# uc4h_cube_carrier_v0310r.net
KiCad netlist of a schematic drawn in EAGLE
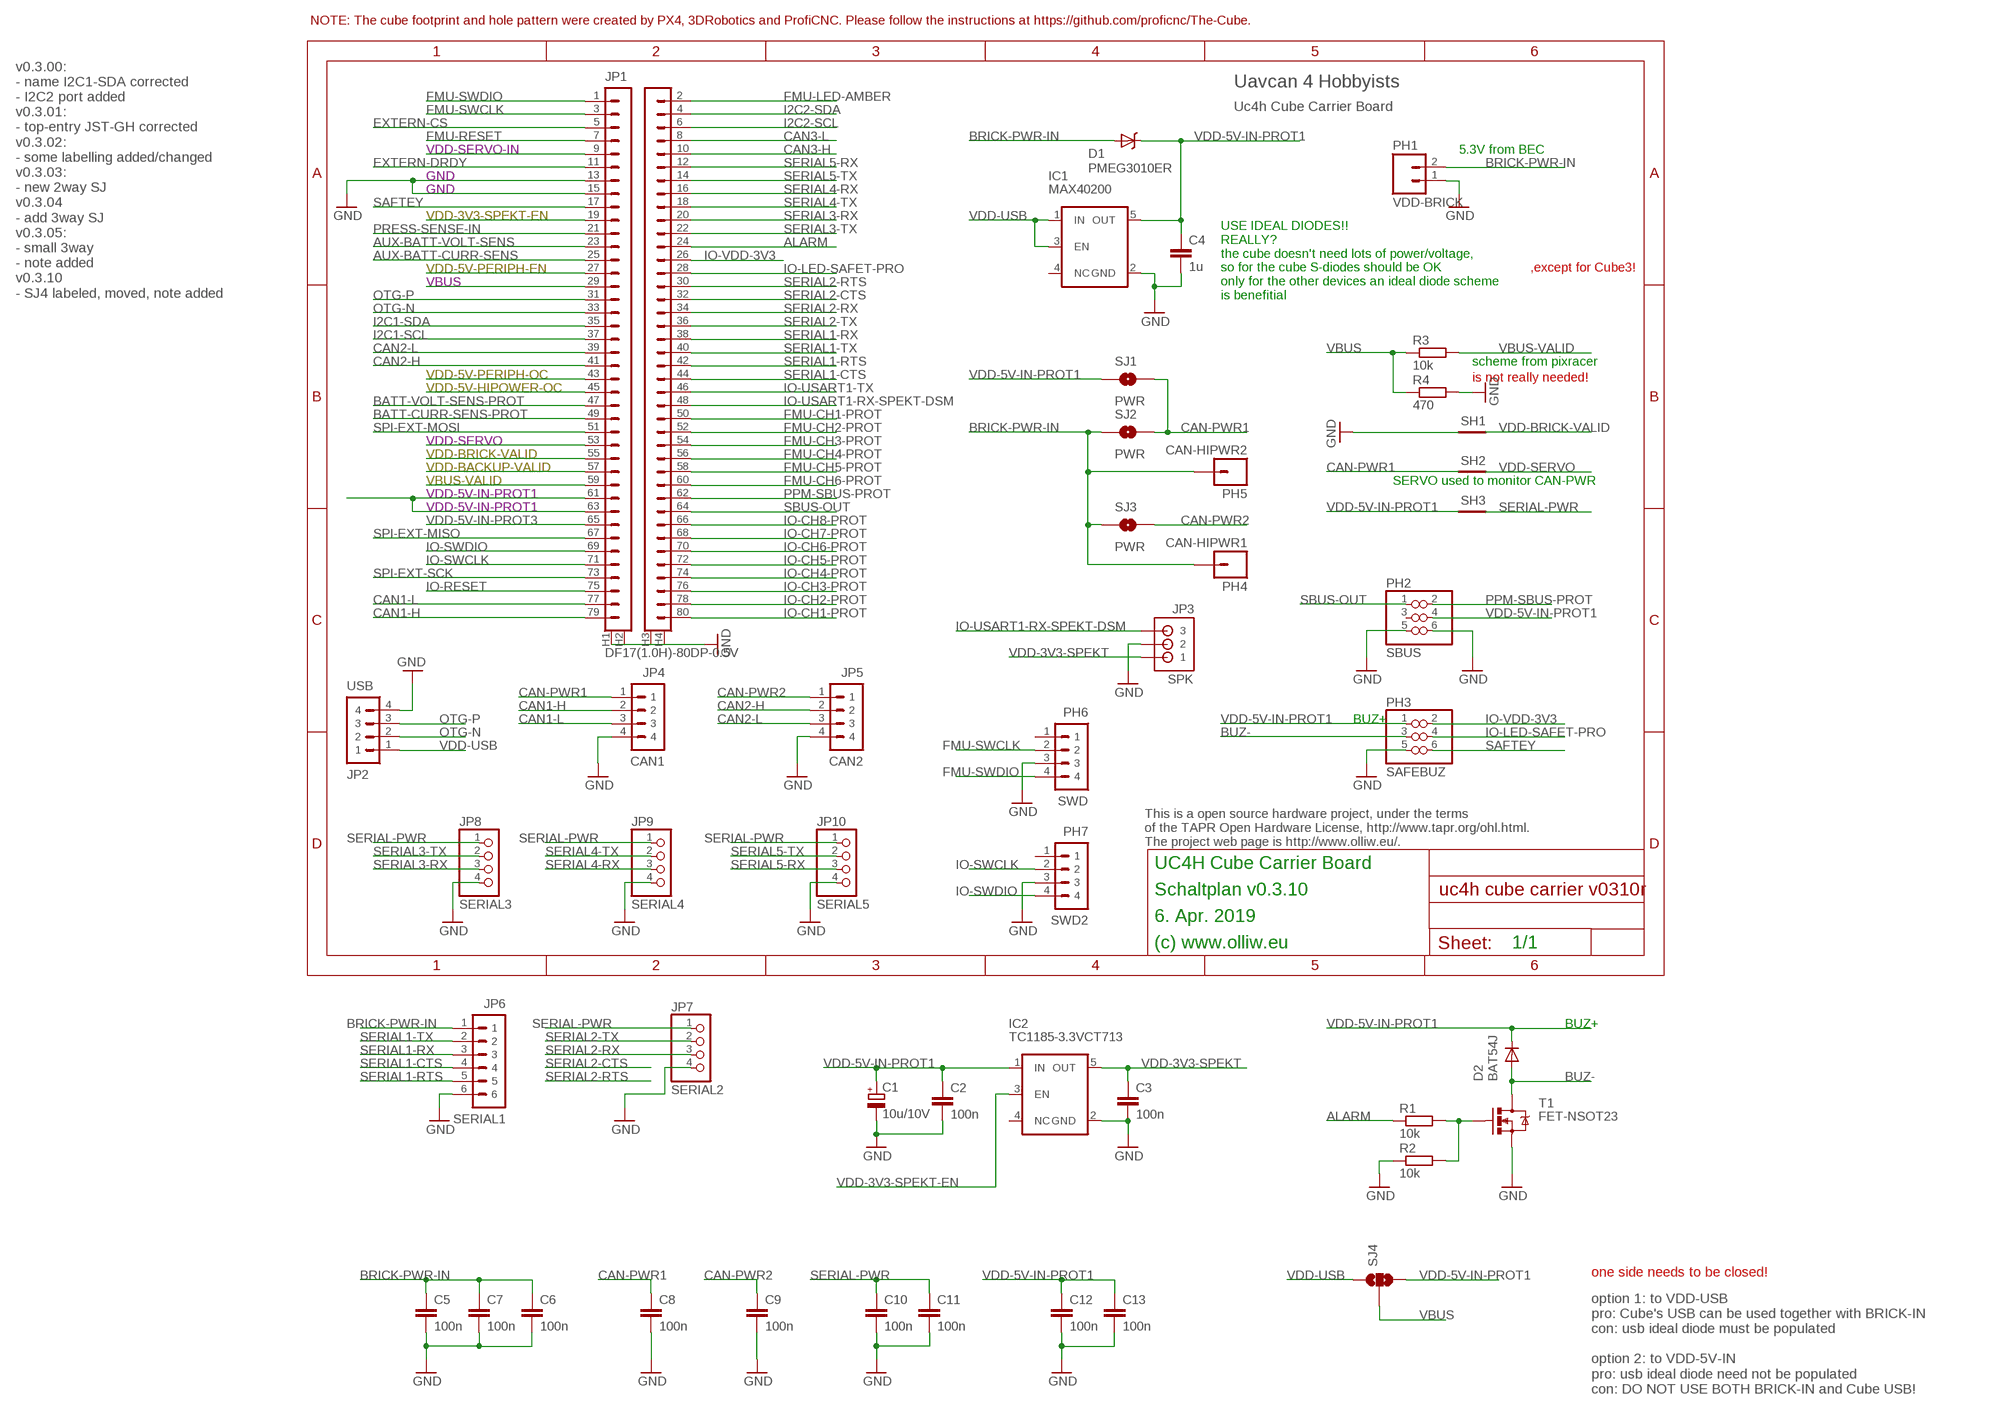
[diagram p0: schematic, sheet 1]

(export (version "E")
  (design (tool "Eeschema 10.0.6"))
  (components
    (comp (ref "C1")
      (value "10u/10V")
      (footprint "eagle-import:SMC_A")
      (libsource (lib "eagle-import") (part "CPOL-EUSMCA"))
    )
    (comp (ref "C2")
      (value "100n")
      (footprint "eagle-import:C0603")
      (libsource (lib "eagle-import") (part "C-EUC0603"))
    )
    (comp (ref "C3")
      (value "100n")
      (footprint "eagle-import:C0603")
      (libsource (lib "eagle-import") (part "C-EUC0603"))
    )
    (comp (ref "C4")
      (value "1u")
      (footprint "eagle-import:C0603")
      (libsource (lib "eagle-import") (part "C-EUC0603"))
    )
    (comp (ref "C5")
      (value "100n")
      (footprint "eagle-import:C0603")
      (libsource (lib "eagle-import") (part "C-EUC0603"))
    )
    (comp (ref "C6")
      (value "100n")
      (footprint "eagle-import:C0603")
      (libsource (lib "eagle-import") (part "C-EUC0603"))
    )
    (comp (ref "C7")
      (value "100n")
      (footprint "eagle-import:C0402")
      (libsource (lib "eagle-import") (part "C-EUC0402"))
    )
    (comp (ref "C8")
      (value "100n")
      (footprint "eagle-import:C0603")
      (libsource (lib "eagle-import") (part "C-EUC0603"))
    )
    (comp (ref "C9")
      (value "100n")
      (footprint "eagle-import:C0603")
      (libsource (lib "eagle-import") (part "C-EUC0603"))
    )
    (comp (ref "C10")
      (value "100n")
      (footprint "eagle-import:C0603")
      (libsource (lib "eagle-import") (part "C-EUC0603"))
    )
    (comp (ref "C11")
      (value "100n")
      (footprint "eagle-import:C0603")
      (libsource (lib "eagle-import") (part "C-EUC0603"))
    )
    (comp (ref "C12")
      (value "100n")
      (footprint "eagle-import:C0603")
      (libsource (lib "eagle-import") (part "C-EUC0603"))
    )
    (comp (ref "C13")
      (value "100n")
      (footprint "eagle-import:C0603")
      (libsource (lib "eagle-import") (part "C-EUC0603"))
    )
    (comp (ref "D1")
      (value "PMEG3010ER")
      (footprint "eagle-import:SOD123W-DIODE")
      (libsource (lib "eagle-import") (part "DIODE-SCHOTTKYSOD123-W"))
    )
    (comp (ref "D2")
      (value "BAT54J")
      (footprint "eagle-import:SOD110-R")
      (libsource (lib "eagle-import") (part "DIODE-SOD110-R"))
    )
    (comp (ref "IC1")
      (value "MAX40200")
      (footprint "eagle-import:SOT23-5")
      (libsource (lib "eagle-import") (part "V_REG_TPS76433SOT23-5"))
    )
    (comp (ref "IC2")
      (value "TC1185-3.3VCT713")
      (footprint "eagle-import:SOT23-5")
      (libsource (lib "eagle-import") (part "V_REG_TPS76433SOT23-5"))
    )
    (comp (ref "JP1")
      (value "DF17(1.0H)-80DP-0.5V")
      (footprint "eagle-import:PIX-CUBE-DF17(1.0H)-80DP-0.5V-VIA")
      (libsource (lib "eagle-import") (part "PIX-CUBE-VIA"))
    )
    (comp (ref "JP2")
      (value "USB")
      (footprint "eagle-import:BM04B-GHS-TBT")
      (libsource (lib "eagle-import") (part "JST-GH-4TOP-ENTRY"))
    )
    (comp (ref "JP3")
      (value "SPK")
      (footprint "eagle-import:B3B-ZR")
      (libsource (lib "eagle-import") (part "B3B-ZR"))
    )
    (comp (ref "JP4")
      (value "CAN1")
      (footprint "eagle-import:BM04B-GHS-TBT")
      (libsource (lib "eagle-import") (part "JST-GH-4TOP-ENTRY"))
    )
    (comp (ref "JP5")
      (value "CAN2")
      (footprint "eagle-import:BM04B-GHS-TBT")
      (libsource (lib "eagle-import") (part "JST-GH-4TOP-ENTRY"))
    )
    (comp (ref "JP6")
      (value "SERIAL1")
      (footprint "eagle-import:BM06B-GHS-TBT")
      (libsource (lib "eagle-import") (part "JST-GH-6TOP-ENTRY"))
    )
    (comp (ref "JP7")
      (value "SERIAL2")
      (footprint "eagle-import:PINHEAD_4X1")
      (libsource (lib "eagle-import") (part "PINHEAD_4X1"))
    )
    (comp (ref "JP8")
      (value "SERIAL3")
      (footprint "eagle-import:PINHEAD_4X1")
      (libsource (lib "eagle-import") (part "PINHEAD_4X1"))
    )
    (comp (ref "JP9")
      (value "SERIAL4")
      (footprint "eagle-import:PINHEAD_4X1")
      (libsource (lib "eagle-import") (part "PINHEAD_4X1"))
    )
    (comp (ref "JP10")
      (value "SERIAL5")
      (footprint "eagle-import:PINHEAD_4X1")
      (libsource (lib "eagle-import") (part "PINHEAD_4X1"))
    )
    (comp (ref "PH1")
      (value "VDD-BRICK")
      (footprint "eagle-import:1X02")
      (libsource (lib "eagle-import") (part "M02PTH"))
    )
    (comp (ref "PH2")
      (value "SBUS")
      (footprint "eagle-import:PINHEAD_3X2")
      (libsource (lib "eagle-import") (part "PINHEAD_3X2"))
    )
    (comp (ref "PH3")
      (value "SAFEBUZ")
      (footprint "eagle-import:PINHEAD_3X2")
      (libsource (lib "eagle-import") (part "PINHEAD_3X2"))
    )
    (comp (ref "PH4")
      (value "CAN-HIPWR1")
      (footprint "eagle-import:1X01")
      (libsource (lib "eagle-import") (part "M01PTH"))
    )
    (comp (ref "PH5")
      (value "CAN-HIPWR2")
      (footprint "eagle-import:1X01")
      (libsource (lib "eagle-import") (part "M01PTH"))
    )
    (comp (ref "PH6")
      (value "SWD")
      (footprint "eagle-import:4X1_1P27_OCT_BILEX")
      (libsource (lib "eagle-import") (part "P4X1_1P27-OCT_BILEX"))
    )
    (comp (ref "PH7")
      (value "SWD2")
      (footprint "eagle-import:4X1_1P27_OCT_BILEX")
      (libsource (lib "eagle-import") (part "P4X1_1P27-OCT_BILEX"))
    )
    (comp (ref "R1")
      (value "10k")
      (footprint "eagle-import:R0402")
      (libsource (lib "eagle-import") (part "R-EU_R0402"))
    )
    (comp (ref "R2")
      (value "10k")
      (footprint "eagle-import:R0402")
      (libsource (lib "eagle-import") (part "R-EU_R0402"))
    )
    (comp (ref "R3")
      (value "10k")
      (footprint "eagle-import:R0402")
      (libsource (lib "eagle-import") (part "R-EU_R0402"))
    )
    (comp (ref "R4")
      (value "470")
      (footprint "eagle-import:R0402")
      (libsource (lib "eagle-import") (part "R-EU_R0402"))
    )
    (comp (ref "SH1")
      (value "SHORT-HT5")
      (footprint "eagle-import:SHORT_TOP-50")
      (libsource (lib "eagle-import") (part "SHORT-HT5"))
    )
    (comp (ref "SH2")
      (value "SHORT-HT5")
      (footprint "eagle-import:SHORT_TOP-50")
      (libsource (lib "eagle-import") (part "SHORT-HT5"))
    )
    (comp (ref "SH3")
      (value "SHORT-HT5")
      (footprint "eagle-import:SHORT_TOP-50")
      (libsource (lib "eagle-import") (part "SHORT-HT5"))
    )
    (comp (ref "SJ1")
      (value "PWR")
      (footprint "eagle-import:SJ-2WAY-BIG-WPASTEC")
      (libsource (lib "eagle-import") (part "SJ-2WAY-WPASTECONNECT"))
    )
    (comp (ref "SJ2")
      (value "PWR")
      (footprint "eagle-import:SJ-2WAY-BIG")
      (libsource (lib "eagle-import") (part "SJ-2WAY-STANDARD"))
    )
    (comp (ref "SJ3")
      (value "PWR")
      (footprint "eagle-import:SJ-2WAY-BIG-WPASTEC")
      (libsource (lib "eagle-import") (part "SJ-2WAY-WPASTECONNECT"))
    )
    (comp (ref "SJ4")
      (value "SJ-3WAY-03")
      (footprint "eagle-import:SJ-3WAY-WPASTEC")
      (libsource (lib "eagle-import") (part "SJ-3WAY-03"))
    )
    (comp (ref "T1")
      (value "FET-NSOT23")
      (footprint "eagle-import:SOT23")
      (libsource (lib "eagle-import") (part "FET-NSOT23"))
    )
  )
  (nets
    (net (code "1") (name "/ALARM") (class "Default")
      (node (ref "JP1") (pin "24") (pinfunction "24_24") (pintype "passive"))
      (node (ref "R1") (pin "1") (pinfunction "1_1") (pintype "passive"))
    )
    (net (code "2") (name "/AUX-BATT-CURR-SENS") (class "Default")
      (node (ref "JP1") (pin "25") (pinfunction "25_25") (pintype "passive"))
    )
    (net (code "3") (name "/AUX-BATT-VOLT-SENS") (class "Default")
      (node (ref "JP1") (pin "23") (pinfunction "23_23") (pintype "passive"))
    )
    (net (code "4") (name "/BATT-CURR-SENS-PROT") (class "Default")
      (node (ref "JP1") (pin "49") (pinfunction "49_49") (pintype "passive"))
    )
    (net (code "5") (name "/BATT-VOLT-SENS-PROT") (class "Default")
      (node (ref "JP1") (pin "47") (pinfunction "47_47") (pintype "passive"))
    )
    (net (code "6") (name "/BRICK-PWR-IN") (class "Default")
      (node (ref "C5") (pin "1") (pinfunction "1_1") (pintype "passive"))
      (node (ref "C6") (pin "1") (pinfunction "1_1") (pintype "passive"))
      (node (ref "C7") (pin "1") (pinfunction "1_1") (pintype "passive"))
      (node (ref "D1") (pin "A") (pinfunction "A_A") (pintype "passive"))
      (node (ref "JP6") (pin "1") (pinfunction "1_1") (pintype "passive"))
      (node (ref "PH1") (pin "2") (pinfunction "2_2") (pintype "passive"))
      (node (ref "PH4") (pin "1") (pinfunction "1_1") (pintype "passive"))
      (node (ref "PH5") (pin "1") (pinfunction "1_1") (pintype "passive"))
      (node (ref "SJ2") (pin "1") (pinfunction "1_1") (pintype "passive"))
      (node (ref "SJ3") (pin "1") (pinfunction "1_1") (pintype "passive"))
    )
    (net (code "7") (name "/BUZ-") (class "Default")
      (node (ref "D2") (pin "A") (pinfunction "A_A") (pintype "passive"))
      (node (ref "PH3") (pin "3") (pinfunction "3_3") (pintype "passive"))
      (node (ref "T1") (pin "3") (pinfunction "D_3") (pintype "passive"))
    )
    (net (code "8") (name "/CAN-PWR1") (class "Default")
      (node (ref "C8") (pin "1") (pinfunction "1_1") (pintype "passive"))
      (node (ref "JP4") (pin "1") (pinfunction "1_1") (pintype "passive"))
      (node (ref "SH2") (pin "1") (pinfunction "P$1_1") (pintype "bidirectional"))
      (node (ref "SJ1") (pin "2") (pinfunction "2_2") (pintype "passive"))
      (node (ref "SJ2") (pin "2") (pinfunction "2_2") (pintype "passive"))
    )
    (net (code "9") (name "/CAN-PWR2") (class "Default")
      (node (ref "C9") (pin "1") (pinfunction "1_1") (pintype "passive"))
      (node (ref "JP5") (pin "1") (pinfunction "1_1") (pintype "passive"))
      (node (ref "SJ3") (pin "2") (pinfunction "2_2") (pintype "passive"))
    )
    (net (code "10") (name "/CAN1-H") (class "Default")
      (node (ref "JP1") (pin "79") (pinfunction "79_79") (pintype "passive"))
      (node (ref "JP4") (pin "2") (pinfunction "2_2") (pintype "passive"))
    )
    (net (code "11") (name "/CAN1-L") (class "Default")
      (node (ref "JP1") (pin "77") (pinfunction "77_77") (pintype "passive"))
      (node (ref "JP4") (pin "3") (pinfunction "3_3") (pintype "passive"))
    )
    (net (code "12") (name "/CAN2-H") (class "Default")
      (node (ref "JP1") (pin "41") (pinfunction "41_41") (pintype "passive"))
      (node (ref "JP5") (pin "2") (pinfunction "2_2") (pintype "passive"))
    )
    (net (code "13") (name "/CAN2-L") (class "Default")
      (node (ref "JP1") (pin "39") (pinfunction "39_39") (pintype "passive"))
      (node (ref "JP5") (pin "3") (pinfunction "3_3") (pintype "passive"))
    )
    (net (code "14") (name "/CAN3-H") (class "Default")
      (node (ref "JP1") (pin "10") (pinfunction "10_10") (pintype "passive"))
    )
    (net (code "15") (name "/CAN3-L") (class "Default")
      (node (ref "JP1") (pin "8") (pinfunction "8_8") (pintype "passive"))
    )
    (net (code "16") (name "/EXTERN-CS") (class "Default")
      (node (ref "JP1") (pin "5") (pinfunction "5_5") (pintype "passive"))
    )
    (net (code "17") (name "/EXTERN-DRDY") (class "Default")
      (node (ref "JP1") (pin "11") (pinfunction "11_11") (pintype "passive"))
    )
    (net (code "18") (name "/FMU-CH1-PROT") (class "Default")
      (node (ref "JP1") (pin "50") (pinfunction "50_50") (pintype "passive"))
    )
    (net (code "19") (name "/FMU-CH2-PROT") (class "Default")
      (node (ref "JP1") (pin "52") (pinfunction "52_52") (pintype "passive"))
    )
    (net (code "20") (name "/FMU-CH3-PROT") (class "Default")
      (node (ref "JP1") (pin "54") (pinfunction "54_54") (pintype "passive"))
    )
    (net (code "21") (name "/FMU-CH4-PROT") (class "Default")
      (node (ref "JP1") (pin "56") (pinfunction "56_56") (pintype "passive"))
    )
    (net (code "22") (name "/FMU-CH5-PROT") (class "Default")
      (node (ref "JP1") (pin "58") (pinfunction "58_58") (pintype "passive"))
    )
    (net (code "23") (name "/FMU-CH6-PROT") (class "Default")
      (node (ref "JP1") (pin "60") (pinfunction "60_60") (pintype "passive"))
    )
    (net (code "24") (name "/FMU-LED-AMBER") (class "Default")
      (node (ref "JP1") (pin "2") (pinfunction "2_2") (pintype "passive"))
    )
    (net (code "25") (name "/FMU-RESET") (class "Default")
      (node (ref "JP1") (pin "7") (pinfunction "7_7") (pintype "passive"))
    )
    (net (code "26") (name "/FMU-SWCLK") (class "Default")
      (node (ref "JP1") (pin "3") (pinfunction "3_3") (pintype "passive"))
      (node (ref "PH6") (pin "2") (pinfunction "2_2") (pintype "passive"))
    )
    (net (code "27") (name "/FMU-SWDIO") (class "Default")
      (node (ref "JP1") (pin "1") (pinfunction "1_1") (pintype "passive"))
      (node (ref "PH6") (pin "4") (pinfunction "4_4") (pintype "passive"))
    )
    (net (code "28") (name "/I2C1-SCL") (class "Default")
      (node (ref "JP1") (pin "37") (pinfunction "37_37") (pintype "passive"))
    )
    (net (code "29") (name "/I2C1-SDA") (class "Default")
      (node (ref "JP1") (pin "35") (pinfunction "35_35") (pintype "passive"))
    )
    (net (code "30") (name "/I2C2-SCL") (class "Default")
      (node (ref "JP1") (pin "6") (pinfunction "6_6") (pintype "passive"))
    )
    (net (code "31") (name "/I2C2-SDA") (class "Default")
      (node (ref "JP1") (pin "4") (pinfunction "4_4") (pintype "passive"))
    )
    (net (code "32") (name "/IO-CH1-PROT") (class "Default")
      (node (ref "JP1") (pin "80") (pinfunction "80_80") (pintype "passive"))
    )
    (net (code "33") (name "/IO-CH2-PROT") (class "Default")
      (node (ref "JP1") (pin "78") (pinfunction "78_78") (pintype "passive"))
    )
    (net (code "34") (name "/IO-CH3-PROT") (class "Default")
      (node (ref "JP1") (pin "76") (pinfunction "76_76") (pintype "passive"))
    )
    (net (code "35") (name "/IO-CH4-PROT") (class "Default")
      (node (ref "JP1") (pin "74") (pinfunction "74_74") (pintype "passive"))
    )
    (net (code "36") (name "/IO-CH5-PROT") (class "Default")
      (node (ref "JP1") (pin "72") (pinfunction "72_72") (pintype "passive"))
    )
    (net (code "37") (name "/IO-CH6-PROT") (class "Default")
      (node (ref "JP1") (pin "70") (pinfunction "70_70") (pintype "passive"))
    )
    (net (code "38") (name "/IO-CH7-PROT") (class "Default")
      (node (ref "JP1") (pin "68") (pinfunction "68_68") (pintype "passive"))
    )
    (net (code "39") (name "/IO-CH8-PROT") (class "Default")
      (node (ref "JP1") (pin "66") (pinfunction "66_66") (pintype "passive"))
    )
    (net (code "40") (name "/IO-LED-SAFET-PRO") (class "Default")
      (node (ref "JP1") (pin "28") (pinfunction "28_28") (pintype "passive"))
      (node (ref "PH3") (pin "4") (pinfunction "4_4") (pintype "passive"))
    )
    (net (code "41") (name "/IO-RESET") (class "Default")
      (node (ref "JP1") (pin "75") (pinfunction "75_75") (pintype "passive"))
    )
    (net (code "42") (name "/IO-SWCLK") (class "Default")
      (node (ref "JP1") (pin "71") (pinfunction "71_71") (pintype "passive"))
      (node (ref "PH7") (pin "2") (pinfunction "2_2") (pintype "passive"))
    )
    (net (code "43") (name "/IO-SWDIO") (class "Default")
      (node (ref "JP1") (pin "69") (pinfunction "69_69") (pintype "passive"))
      (node (ref "PH7") (pin "4") (pinfunction "4_4") (pintype "passive"))
    )
    (net (code "44") (name "/IO-USART1-RX-SPEKT-DSM") (class "Default")
      (node (ref "JP1") (pin "48") (pinfunction "48_48") (pintype "passive"))
      (node (ref "JP3") (pin "3") (pinfunction "3_3") (pintype "bidirectional"))
    )
    (net (code "45") (name "/IO-USART1-TX") (class "Default")
      (node (ref "JP1") (pin "46") (pinfunction "46_46") (pintype "passive"))
    )
    (net (code "46") (name "/IO-VDD-3V3") (class "Default")
      (node (ref "JP1") (pin "26") (pinfunction "26_26") (pintype "passive"))
      (node (ref "PH3") (pin "2") (pinfunction "2_2") (pintype "passive"))
    )
    (net (code "47") (name "/OTG-N") (class "Default")
      (node (ref "JP1") (pin "33") (pinfunction "33_33") (pintype "passive"))
      (node (ref "JP2") (pin "2") (pinfunction "2_2") (pintype "passive"))
    )
    (net (code "48") (name "/OTG-P") (class "Default")
      (node (ref "JP1") (pin "31") (pinfunction "31_31") (pintype "passive"))
      (node (ref "JP2") (pin "3") (pinfunction "3_3") (pintype "passive"))
    )
    (net (code "49") (name "/PPM-SBUS-PROT") (class "Default")
      (node (ref "JP1") (pin "62") (pinfunction "62_62") (pintype "passive"))
      (node (ref "PH2") (pin "2") (pinfunction "2_2") (pintype "passive"))
    )
    (net (code "50") (name "/PRESS-SENSE-IN") (class "Default")
      (node (ref "JP1") (pin "21") (pinfunction "21_21") (pintype "passive"))
    )
    (net (code "51") (name "/SAFTEY") (class "Default")
      (node (ref "JP1") (pin "17") (pinfunction "17_17") (pintype "passive"))
      (node (ref "PH3") (pin "6") (pinfunction "6_6") (pintype "passive"))
    )
    (net (code "52") (name "/SBUS-OUT") (class "Default")
      (node (ref "JP1") (pin "64") (pinfunction "64_64") (pintype "passive"))
      (node (ref "PH2") (pin "1") (pinfunction "1_1") (pintype "passive"))
    )
    (net (code "53") (name "/SERIAL-PWR") (class "Default")
      (node (ref "C10") (pin "1") (pinfunction "1_1") (pintype "passive"))
      (node (ref "C11") (pin "1") (pinfunction "1_1") (pintype "passive"))
      (node (ref "JP10") (pin "1") (pinfunction "1_1") (pintype "passive"))
      (node (ref "JP7") (pin "1") (pinfunction "1_1") (pintype "passive"))
      (node (ref "JP8") (pin "1") (pinfunction "1_1") (pintype "passive"))
      (node (ref "JP9") (pin "1") (pinfunction "1_1") (pintype "passive"))
      (node (ref "SH3") (pin "2") (pinfunction "P$2_2") (pintype "bidirectional"))
    )
    (net (code "54") (name "/SERIAL1-CTS") (class "Default")
      (node (ref "JP1") (pin "44") (pinfunction "44_44") (pintype "passive"))
      (node (ref "JP6") (pin "4") (pinfunction "4_4") (pintype "passive"))
    )
    (net (code "55") (name "/SERIAL1-RTS") (class "Default")
      (node (ref "JP1") (pin "42") (pinfunction "42_42") (pintype "passive"))
      (node (ref "JP6") (pin "5") (pinfunction "5_5") (pintype "passive"))
    )
    (net (code "56") (name "/SERIAL1-RX") (class "Default")
      (node (ref "JP1") (pin "38") (pinfunction "38_38") (pintype "passive"))
      (node (ref "JP6") (pin "3") (pinfunction "3_3") (pintype "passive"))
    )
    (net (code "57") (name "/SERIAL1-TX") (class "Default")
      (node (ref "JP1") (pin "40") (pinfunction "40_40") (pintype "passive"))
      (node (ref "JP6") (pin "2") (pinfunction "2_2") (pintype "passive"))
    )
    (net (code "58") (name "/SERIAL2-CTS") (class "Default")
      (node (ref "JP1") (pin "32") (pinfunction "32_32") (pintype "passive"))
    )
    (net (code "59") (name "/SERIAL2-RTS") (class "Default")
      (node (ref "JP1") (pin "30") (pinfunction "30_30") (pintype "passive"))
    )
    (net (code "60") (name "/SERIAL2-RX") (class "Default")
      (node (ref "JP1") (pin "34") (pinfunction "34_34") (pintype "passive"))
      (node (ref "JP7") (pin "3") (pinfunction "3_3") (pintype "passive"))
    )
    (net (code "61") (name "/SERIAL2-TX") (class "Default")
      (node (ref "JP1") (pin "36") (pinfunction "36_36") (pintype "passive"))
      (node (ref "JP7") (pin "2") (pinfunction "2_2") (pintype "passive"))
    )
    (net (code "62") (name "/SERIAL3-RX") (class "Default")
      (node (ref "JP1") (pin "20") (pinfunction "20_20") (pintype "passive"))
      (node (ref "JP8") (pin "3") (pinfunction "3_3") (pintype "passive"))
    )
    (net (code "63") (name "/SERIAL3-TX") (class "Default")
      (node (ref "JP1") (pin "22") (pinfunction "22_22") (pintype "passive"))
      (node (ref "JP8") (pin "2") (pinfunction "2_2") (pintype "passive"))
    )
    (net (code "64") (name "/SERIAL4-RX") (class "Default")
      (node (ref "JP1") (pin "16") (pinfunction "16_16") (pintype "passive"))
      (node (ref "JP9") (pin "3") (pinfunction "3_3") (pintype "passive"))
    )
    (net (code "65") (name "/SERIAL4-TX") (class "Default")
      (node (ref "JP1") (pin "18") (pinfunction "18_18") (pintype "passive"))
      (node (ref "JP9") (pin "2") (pinfunction "2_2") (pintype "passive"))
    )
    (net (code "66") (name "/SERIAL5-RX") (class "Default")
      (node (ref "JP1") (pin "12") (pinfunction "12_12") (pintype "passive"))
      (node (ref "JP10") (pin "3") (pinfunction "3_3") (pintype "passive"))
    )
    (net (code "67") (name "/SERIAL5-TX") (class "Default")
      (node (ref "JP1") (pin "14") (pinfunction "14_14") (pintype "passive"))
      (node (ref "JP10") (pin "2") (pinfunction "2_2") (pintype "passive"))
    )
    (net (code "68") (name "/SPI-EXT-MISO") (class "Default")
      (node (ref "JP1") (pin "67") (pinfunction "67_67") (pintype "passive"))
    )
    (net (code "69") (name "/SPI-EXT-MOSI") (class "Default")
      (node (ref "JP1") (pin "51") (pinfunction "51_51") (pintype "passive"))
    )
    (net (code "70") (name "/SPI-EXT-SCK") (class "Default")
      (node (ref "JP1") (pin "73") (pinfunction "73_73") (pintype "passive"))
    )
    (net (code "71") (name "/VBUS") (class "Default")
      (node (ref "JP1") (pin "29") (pinfunction "29_29") (pintype "passive"))
      (node (ref "R3") (pin "1") (pinfunction "1_1") (pintype "passive"))
      (node (ref "R4") (pin "1") (pinfunction "1_1") (pintype "passive"))
      (node (ref "SJ4") (pin "2") (pinfunction "2_2") (pintype "passive"))
    )
    (net (code "72") (name "/VBUS-VALID") (class "Default")
      (node (ref "JP1") (pin "59") (pinfunction "59_59") (pintype "passive"))
      (node (ref "R3") (pin "2") (pinfunction "2_2") (pintype "passive"))
    )
    (net (code "73") (name "/VDD-3V3-SPEKT") (class "Default")
      (node (ref "C3") (pin "1") (pinfunction "1_1") (pintype "passive"))
      (node (ref "IC2") (pin "5") (pinfunction "OUT_5") (pintype "output"))
      (node (ref "JP3") (pin "1") (pinfunction "1_1") (pintype "bidirectional"))
    )
    (net (code "74") (name "/VDD-3V3-SPEKT-EN") (class "Default")
      (node (ref "IC2") (pin "3") (pinfunction "EN_3") (pintype "input"))
      (node (ref "JP1") (pin "19") (pinfunction "19_19") (pintype "passive"))
    )
    (net (code "75") (name "/VDD-5V-HIPOWER-OC") (class "Default")
      (node (ref "JP1") (pin "45") (pinfunction "45_45") (pintype "passive"))
    )
    (net (code "76") (name "/VDD-5V-IN-PROT1") (class "Default")
      (node (ref "C1") (pin "+") (pinfunction "+_+") (pintype "passive"))
      (node (ref "C12") (pin "1") (pinfunction "1_1") (pintype "passive"))
      (node (ref "C13") (pin "1") (pinfunction "1_1") (pintype "passive"))
      (node (ref "C2") (pin "1") (pinfunction "1_1") (pintype "passive"))
      (node (ref "C4") (pin "1") (pinfunction "1_1") (pintype "passive"))
      (node (ref "D1") (pin "C") (pinfunction "C_C") (pintype "passive"))
      (node (ref "D2") (pin "C") (pinfunction "C_C") (pintype "passive"))
      (node (ref "IC1") (pin "5") (pinfunction "OUT_5") (pintype "output"))
      (node (ref "IC2") (pin "1") (pinfunction "IN_1") (pintype "power_in"))
      (node (ref "JP1") (pin "61") (pinfunction "61_61") (pintype "passive"))
      (node (ref "JP1") (pin "63") (pinfunction "63_63") (pintype "passive"))
      (node (ref "PH2") (pin "4") (pinfunction "4_4") (pintype "passive"))
      (node (ref "PH3") (pin "1") (pinfunction "1_1") (pintype "passive"))
      (node (ref "SH3") (pin "1") (pinfunction "P$1_1") (pintype "bidirectional"))
      (node (ref "SJ1") (pin "1") (pinfunction "1_1") (pintype "passive"))
      (node (ref "SJ4") (pin "3") (pinfunction "3_3") (pintype "passive"))
    )
    (net (code "77") (name "/VDD-5V-IN-PROT3") (class "Default")
      (node (ref "JP1") (pin "65") (pinfunction "65_65") (pintype "passive"))
    )
    (net (code "78") (name "/VDD-5V-PERIPH-EN") (class "Default")
      (node (ref "JP1") (pin "27") (pinfunction "27_27") (pintype "passive"))
    )
    (net (code "79") (name "/VDD-5V-PERIPH-OC") (class "Default")
      (node (ref "JP1") (pin "43") (pinfunction "43_43") (pintype "passive"))
    )
    (net (code "80") (name "/VDD-BACKUP-VALID") (class "Default")
      (node (ref "JP1") (pin "57") (pinfunction "57_57") (pintype "passive"))
    )
    (net (code "81") (name "/VDD-BRICK-VALID") (class "Default")
      (node (ref "JP1") (pin "55") (pinfunction "55_55") (pintype "passive"))
      (node (ref "SH1") (pin "2") (pinfunction "P$2_2") (pintype "bidirectional"))
    )
    (net (code "82") (name "/VDD-SERVO") (class "Default")
      (node (ref "JP1") (pin "53") (pinfunction "53_53") (pintype "passive"))
      (node (ref "SH2") (pin "2") (pinfunction "P$2_2") (pintype "bidirectional"))
    )
    (net (code "83") (name "/VDD-SERVO-IN") (class "Default")
      (node (ref "JP1") (pin "9") (pinfunction "9_9") (pintype "passive"))
    )
    (net (code "84") (name "/VDD-USB") (class "Default")
      (node (ref "IC1") (pin "1") (pinfunction "IN_1") (pintype "power_in"))
      (node (ref "IC1") (pin "3") (pinfunction "EN_3") (pintype "input"))
      (node (ref "JP2") (pin "1") (pinfunction "1_1") (pintype "passive"))
      (node (ref "SJ4") (pin "1") (pinfunction "1_1") (pintype "passive"))
    )
    (net (code "85") (name "GND") (class "Default")
      (node (ref "C1") (pin "-") (pinfunction "-_-") (pintype "passive"))
      (node (ref "C10") (pin "2") (pinfunction "2_2") (pintype "passive"))
      (node (ref "C11") (pin "2") (pinfunction "2_2") (pintype "passive"))
      (node (ref "C12") (pin "2") (pinfunction "2_2") (pintype "passive"))
      (node (ref "C13") (pin "2") (pinfunction "2_2") (pintype "passive"))
      (node (ref "C2") (pin "2") (pinfunction "2_2") (pintype "passive"))
      (node (ref "C3") (pin "2") (pinfunction "2_2") (pintype "passive"))
      (node (ref "C4") (pin "2") (pinfunction "2_2") (pintype "passive"))
      (node (ref "C5") (pin "2") (pinfunction "2_2") (pintype "passive"))
      (node (ref "C6") (pin "2") (pinfunction "2_2") (pintype "passive"))
      (node (ref "C7") (pin "2") (pinfunction "2_2") (pintype "passive"))
      (node (ref "C8") (pin "2") (pinfunction "2_2") (pintype "passive"))
      (node (ref "C9") (pin "2") (pinfunction "2_2") (pintype "passive"))
      (node (ref "IC1") (pin "2") (pinfunction "GND_2") (pintype "power_in"))
      (node (ref "IC2") (pin "2") (pinfunction "GND_2") (pintype "power_in"))
      (node (ref "JP1") (pin "13") (pinfunction "13_13") (pintype "passive"))
      (node (ref "JP1") (pin "15") (pinfunction "15_15") (pintype "passive"))
      (node (ref "JP1") (pin "H1") (pinfunction "81_H1") (pintype "passive"))
      (node (ref "JP1") (pin "H2") (pinfunction "82_H2") (pintype "passive"))
      (node (ref "JP1") (pin "H3") (pinfunction "83_H3") (pintype "passive"))
      (node (ref "JP1") (pin "H4") (pinfunction "84_H4") (pintype "passive"))
      (node (ref "JP10") (pin "4") (pinfunction "4_4") (pintype "passive"))
      (node (ref "JP2") (pin "4") (pinfunction "4_4") (pintype "passive"))
      (node (ref "JP3") (pin "2") (pinfunction "2_2") (pintype "bidirectional"))
      (node (ref "JP4") (pin "4") (pinfunction "4_4") (pintype "passive"))
      (node (ref "JP5") (pin "4") (pinfunction "4_4") (pintype "passive"))
      (node (ref "JP6") (pin "6") (pinfunction "6_6") (pintype "passive"))
      (node (ref "JP7") (pin "4") (pinfunction "4_4") (pintype "passive"))
      (node (ref "JP8") (pin "4") (pinfunction "4_4") (pintype "passive"))
      (node (ref "JP9") (pin "4") (pinfunction "4_4") (pintype "passive"))
      (node (ref "PH1") (pin "1") (pinfunction "1_1") (pintype "passive"))
      (node (ref "PH2") (pin "5") (pinfunction "5_5") (pintype "passive"))
      (node (ref "PH2") (pin "6") (pinfunction "6_6") (pintype "passive"))
      (node (ref "PH3") (pin "5") (pinfunction "5_5") (pintype "passive"))
      (node (ref "PH6") (pin "3") (pinfunction "3_3") (pintype "passive"))
      (node (ref "PH7") (pin "3") (pinfunction "3_3") (pintype "passive"))
      (node (ref "R2") (pin "1") (pinfunction "1_1") (pintype "passive"))
      (node (ref "R4") (pin "2") (pinfunction "2_2") (pintype "passive"))
      (node (ref "SH1") (pin "1") (pinfunction "P$1_1") (pintype "bidirectional"))
      (node (ref "T1") (pin "2") (pinfunction "S_2") (pintype "passive"))
    )
    (net (code "86") (name "Net-(T1-G)") (class "Default")
      (node (ref "R1") (pin "2") (pinfunction "2_2") (pintype "passive"))
      (node (ref "R2") (pin "2") (pinfunction "2_2") (pintype "passive"))
      (node (ref "T1") (pin "1") (pinfunction "G_1") (pintype "passive"))
    )
    (net (code "87") (name "unconnected-(IC1-NC-Pad4)") (class "Default")
      (node (ref "IC1") (pin "4") (pinfunction "NC_4") (pintype "passive"))
    )
    (net (code "88") (name "unconnected-(IC2-NC-Pad4)") (class "Default")
      (node (ref "IC2") (pin "4") (pinfunction "NC_4") (pintype "passive"))
    )
    (net (code "89") (name "unconnected-(PH2-Pad3)") (class "Default")
      (node (ref "PH2") (pin "3") (pinfunction "3_3") (pintype "passive"))
    )
    (net (code "90") (name "unconnected-(PH6-Pad1)") (class "Default")
      (node (ref "PH6") (pin "1") (pinfunction "1_1") (pintype "passive"))
    )
    (net (code "91") (name "unconnected-(PH7-Pad1)") (class "Default")
      (node (ref "PH7") (pin "1") (pinfunction "1_1") (pintype "passive"))
    )
  )
)
